# SD_prog.net
KiCad netlist of a schematic drawn in EAGLE
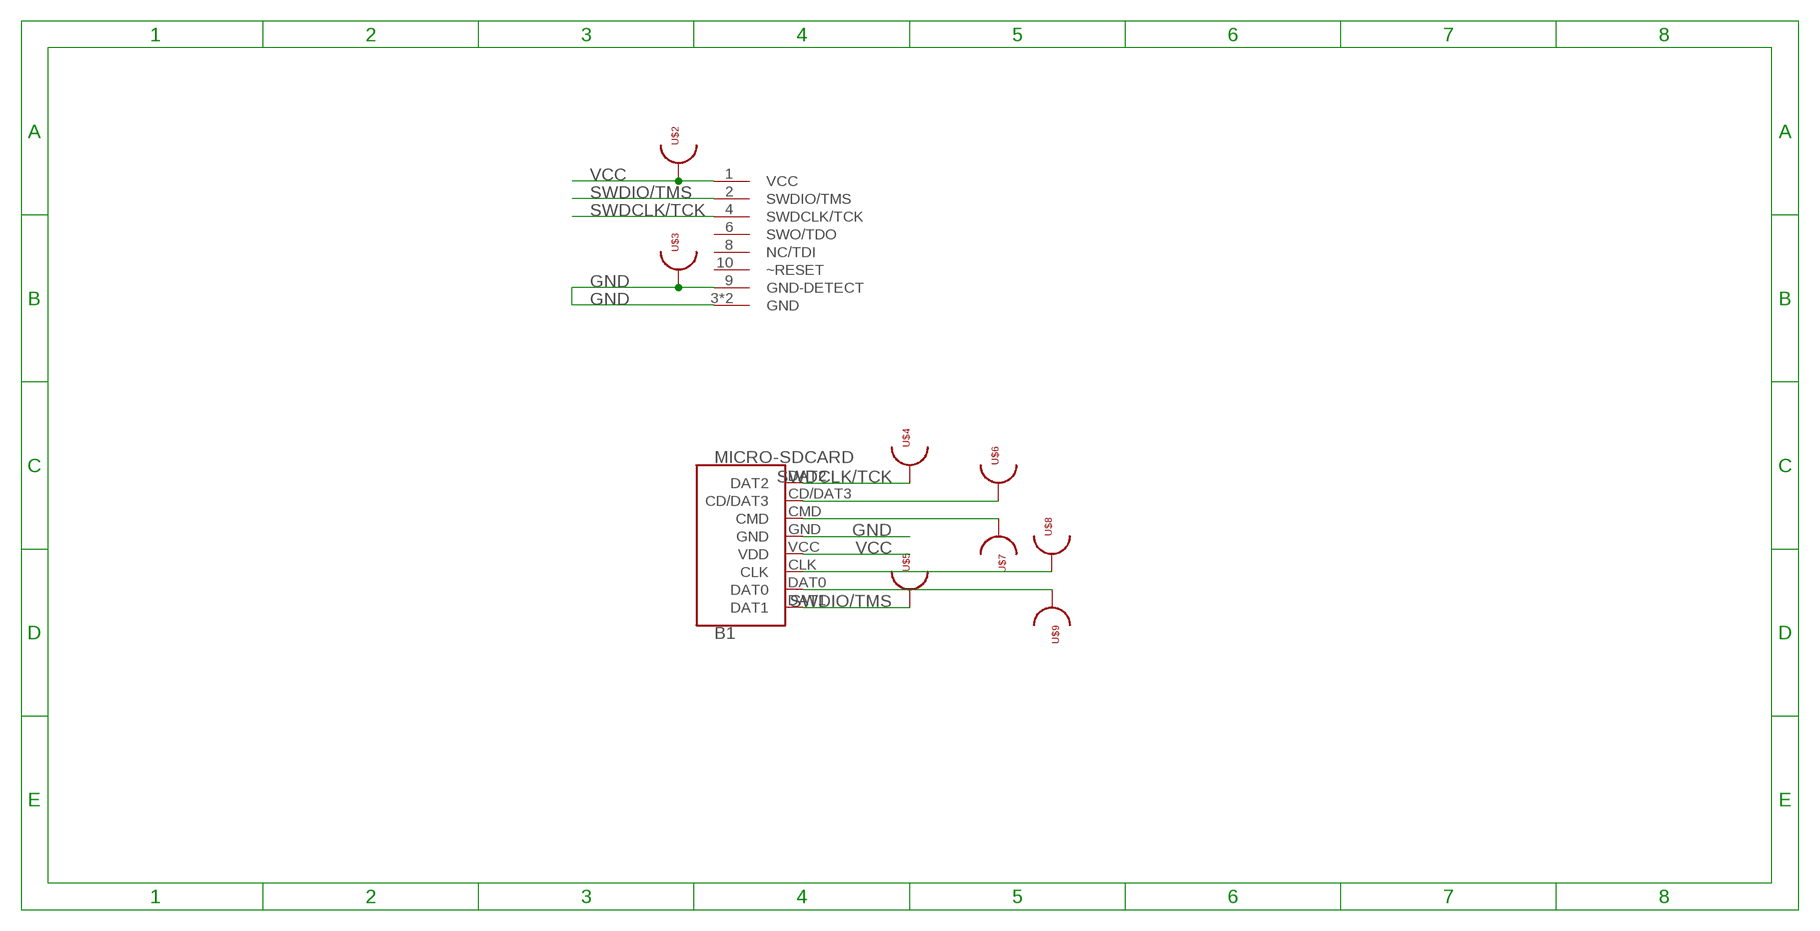
[diagram p0: schematic, sheet 1]

(export (version "E")
  (design (tool "Eeschema 10.0.6"))
  (components
    (comp (ref "B1")
      (value "MICRO-SDCARD")
      (footprint "eagle-import:MICRO-SDCARD")
      (libsource (lib "eagle-import") (part "MICRO-SDCARD"))
    )
    (comp (ref "U$1")
      (value "2X5_0.05\"_CORTEX_DEBUGTH_NOKEY_UNSHROUDED")
      (footprint "eagle-import:2X5_0.05__TH_NS")
      (libsource (lib "eagle-import") (part "2X5_0.05{dblquote}_CORTEX_DEBUGTH_NOKEY_UNSHROUDED"))
    )
    (comp (ref "U$2")
      (value "TESTPOINT_33")
      (footprint "eagle-import:TESTPOINT_33")
      (libsource (lib "eagle-import") (part "TESTPOINT_33"))
    )
    (comp (ref "U$3")
      (value "TESTPOINT_33")
      (footprint "eagle-import:TESTPOINT_33")
      (libsource (lib "eagle-import") (part "TESTPOINT_33"))
    )
    (comp (ref "U$4")
      (value "TESTPOINT_33")
      (footprint "eagle-import:TESTPOINT_33")
      (libsource (lib "eagle-import") (part "TESTPOINT_33"))
    )
    (comp (ref "U$5")
      (value "TESTPOINT_33")
      (footprint "eagle-import:TESTPOINT_33")
      (libsource (lib "eagle-import") (part "TESTPOINT_33"))
    )
    (comp (ref "U$6")
      (value "TESTPOINT_22")
      (footprint "eagle-import:TESTPOINT_22")
      (libsource (lib "eagle-import") (part "TESTPOINT_22"))
    )
    (comp (ref "U$7")
      (value "TESTPOINT_22")
      (footprint "eagle-import:TESTPOINT_22")
      (libsource (lib "eagle-import") (part "TESTPOINT_22"))
    )
    (comp (ref "U$8")
      (value "TESTPOINT_22")
      (footprint "eagle-import:TESTPOINT_22")
      (libsource (lib "eagle-import") (part "TESTPOINT_22"))
    )
    (comp (ref "U$9")
      (value "TESTPOINT_22")
      (footprint "eagle-import:TESTPOINT_22")
      (libsource (lib "eagle-import") (part "TESTPOINT_22"))
    )
  )
  (nets
    (net (code "1") (name "/GND") (class "Default")
      (node (ref "B1") (pin "GND") (pinfunction "GND_GND") (pintype "power_in"))
      (node (ref "U$1") (pin "3") (pinfunction "GND_3") (pintype "bidirectional"))
      (node (ref "U$1") (pin "5") (pinfunction "GND_5") (pintype "bidirectional"))
      (node (ref "U$1") (pin "9") (pinfunction "GND-DETECT_9") (pintype "bidirectional"))
      (node (ref "U$3") (pin "P$1") (pinfunction "P$1_P$1") (pintype "bidirectional"))
    )
    (net (code "2") (name "/SWDCLK{slash}TCK") (class "Default")
      (node (ref "B1") (pin "DAT2") (pinfunction "DAT2_DAT2") (pintype "bidirectional"))
      (node (ref "U$1") (pin "4") (pinfunction "SWDCLK/TCK_4") (pintype "bidirectional"))
      (node (ref "U$4") (pin "P$1") (pinfunction "P$1_P$1") (pintype "bidirectional"))
    )
    (net (code "3") (name "/SWDIO{slash}TMS") (class "Default")
      (node (ref "B1") (pin "DAT1") (pinfunction "DAT1_DAT1") (pintype "bidirectional"))
      (node (ref "U$1") (pin "2") (pinfunction "SWDIO/TMS_2") (pintype "bidirectional"))
      (node (ref "U$5") (pin "P$1") (pinfunction "P$1_P$1") (pintype "bidirectional"))
    )
    (net (code "4") (name "/VCC") (class "Default")
      (node (ref "B1") (pin "VCC") (pinfunction "VDD_VCC") (pintype "power_in"))
      (node (ref "U$1") (pin "1") (pinfunction "VCC_1") (pintype "bidirectional"))
      (node (ref "U$2") (pin "P$1") (pinfunction "P$1_P$1") (pintype "bidirectional"))
    )
    (net (code "5") (name "Net-(B1-PadCD{slash}DAT3)") (class "Default")
      (node (ref "B1") (pin "CD/DAT3") (pinfunction "CD/DAT3_CD/DAT3") (pintype "bidirectional"))
      (node (ref "U$6") (pin "P$1") (pinfunction "P$1_P$1") (pintype "bidirectional"))
    )
    (net (code "6") (name "Net-(B1-PadCLK)") (class "Default")
      (node (ref "B1") (pin "CLK") (pinfunction "CLK_CLK") (pintype "bidirectional"))
      (node (ref "U$8") (pin "P$1") (pinfunction "P$1_P$1") (pintype "bidirectional"))
    )
    (net (code "7") (name "Net-(B1-PadCMD)") (class "Default")
      (node (ref "B1") (pin "CMD") (pinfunction "CMD_CMD") (pintype "bidirectional"))
      (node (ref "U$7") (pin "P$1") (pinfunction "P$1_P$1") (pintype "bidirectional"))
    )
    (net (code "8") (name "Net-(B1-PadDAT0)") (class "Default")
      (node (ref "B1") (pin "DAT0") (pinfunction "DAT0_DAT0") (pintype "bidirectional"))
      (node (ref "U$9") (pin "P$1") (pinfunction "P$1_P$1") (pintype "bidirectional"))
    )
    (net (code "9") (name "unconnected-(U$1-NC{slash}TDI-Pad8)") (class "Default")
      (node (ref "U$1") (pin "8") (pinfunction "NC/TDI_8") (pintype "bidirectional"))
    )
    (net (code "10") (name "unconnected-(U$1-SWO{slash}TDO-Pad6)") (class "Default")
      (node (ref "U$1") (pin "6") (pinfunction "SWO/TDO_6") (pintype "bidirectional"))
    )
    (net (code "11") (name "unconnected-(U$1-~{RESET}-Pad10)") (class "Default")
      (node (ref "U$1") (pin "10") (pinfunction "~{RESET}_10") (pintype "bidirectional"))
    )
  )
)
